# du-ino.net
KiCad netlist of a schematic drawn in EAGLE
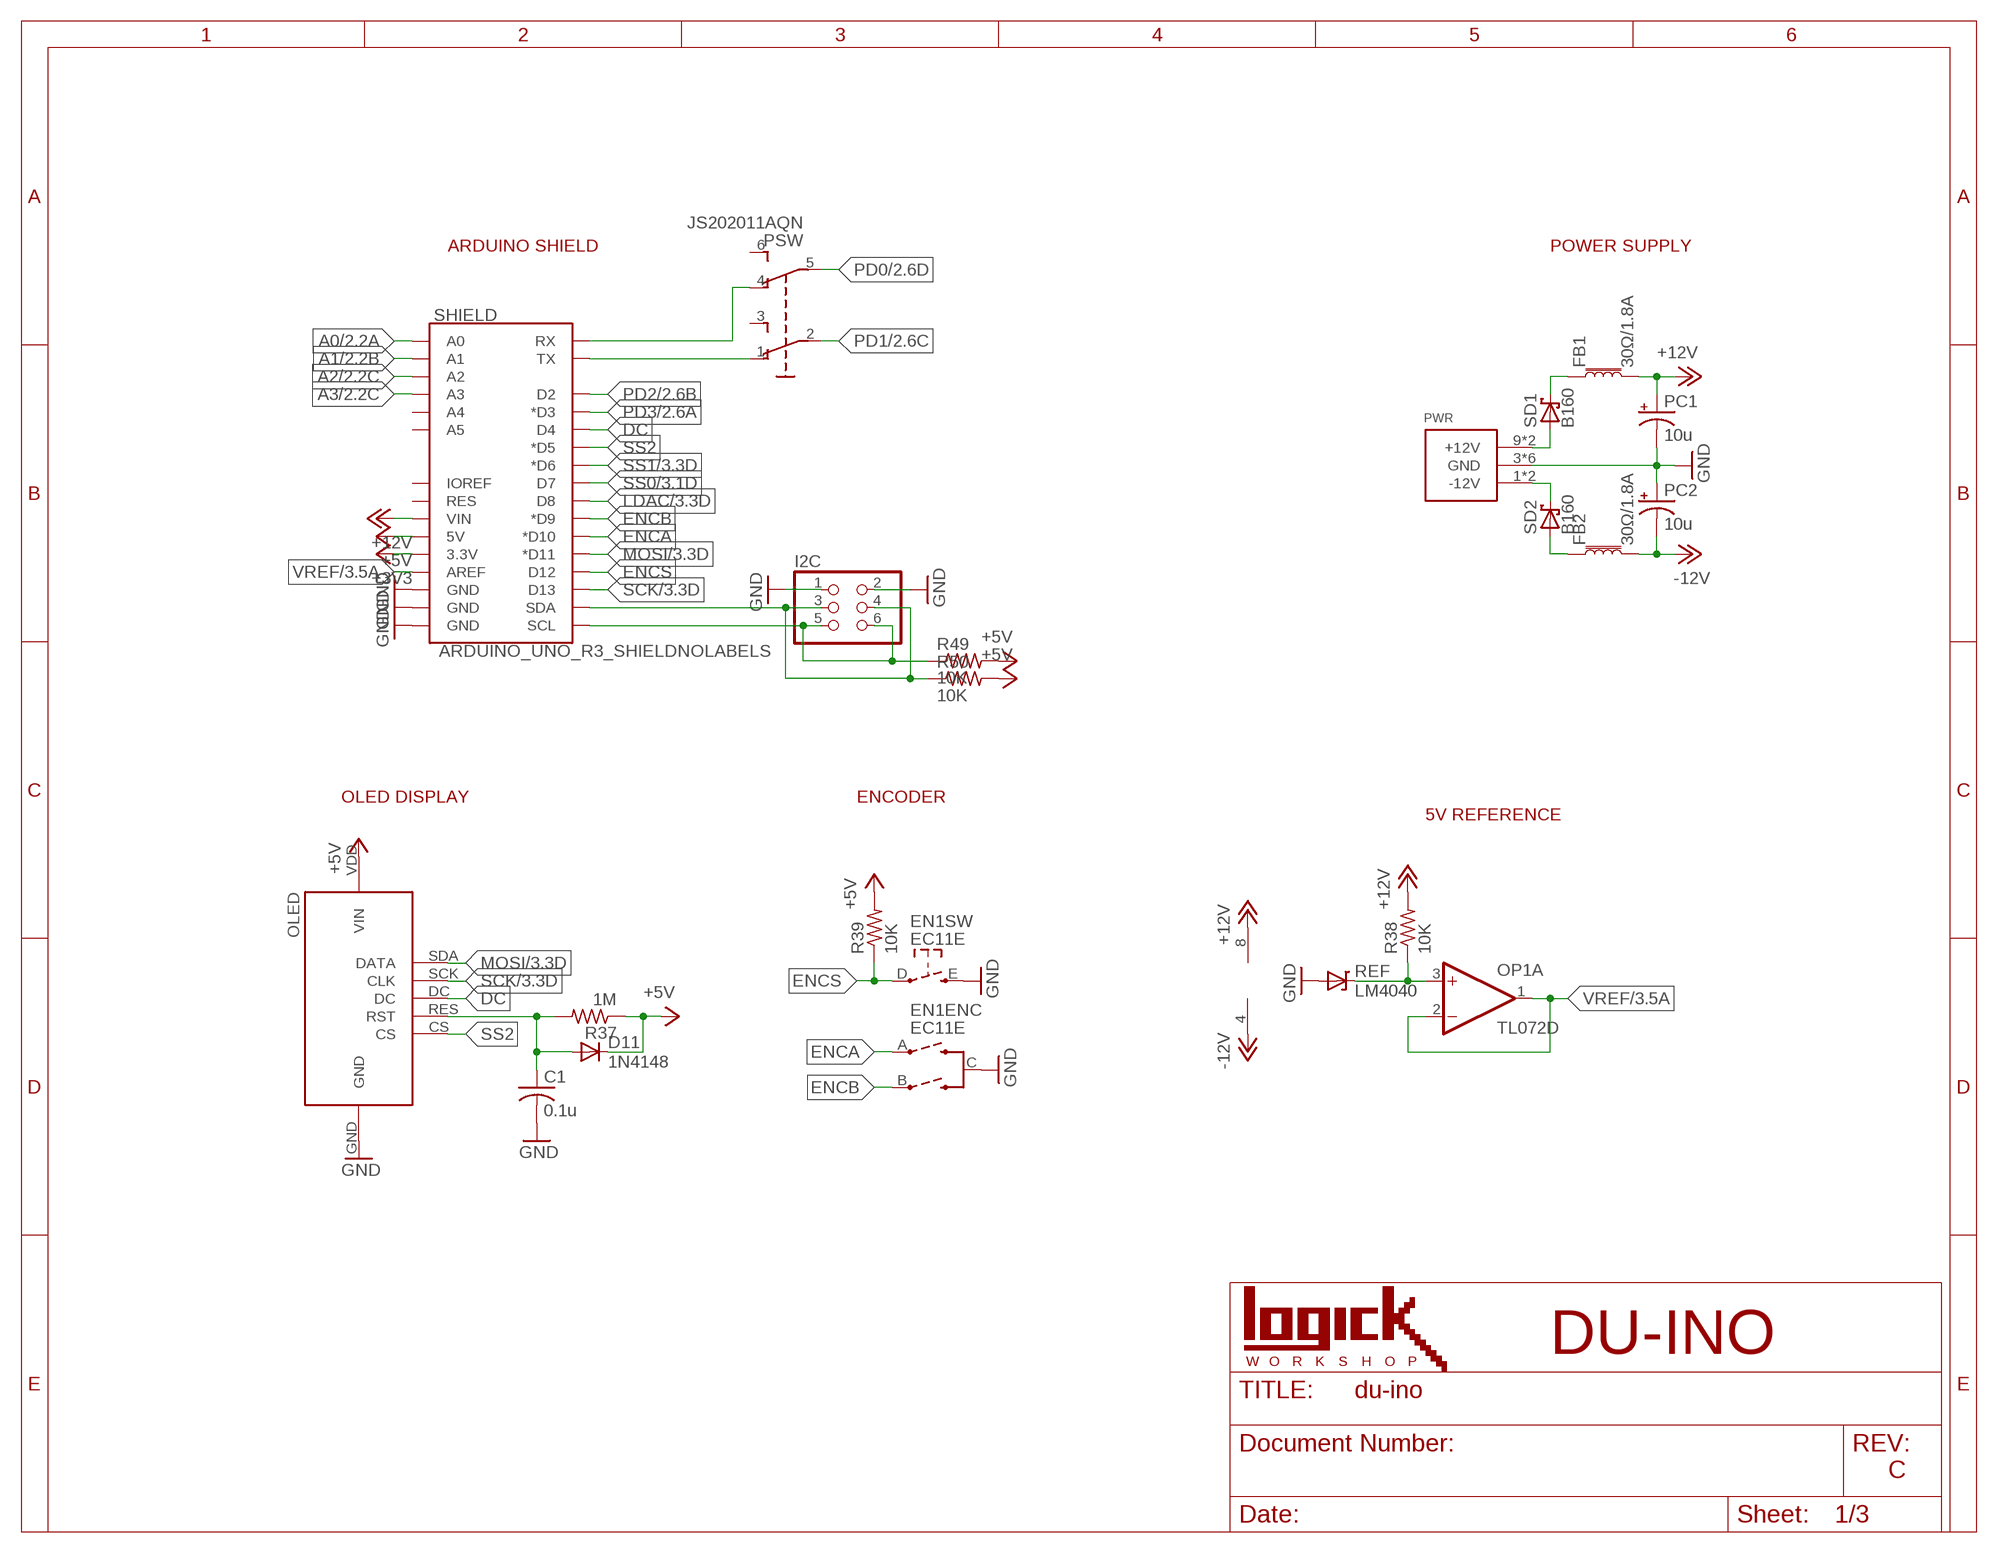
[diagram p0: schematic, sheet 1]
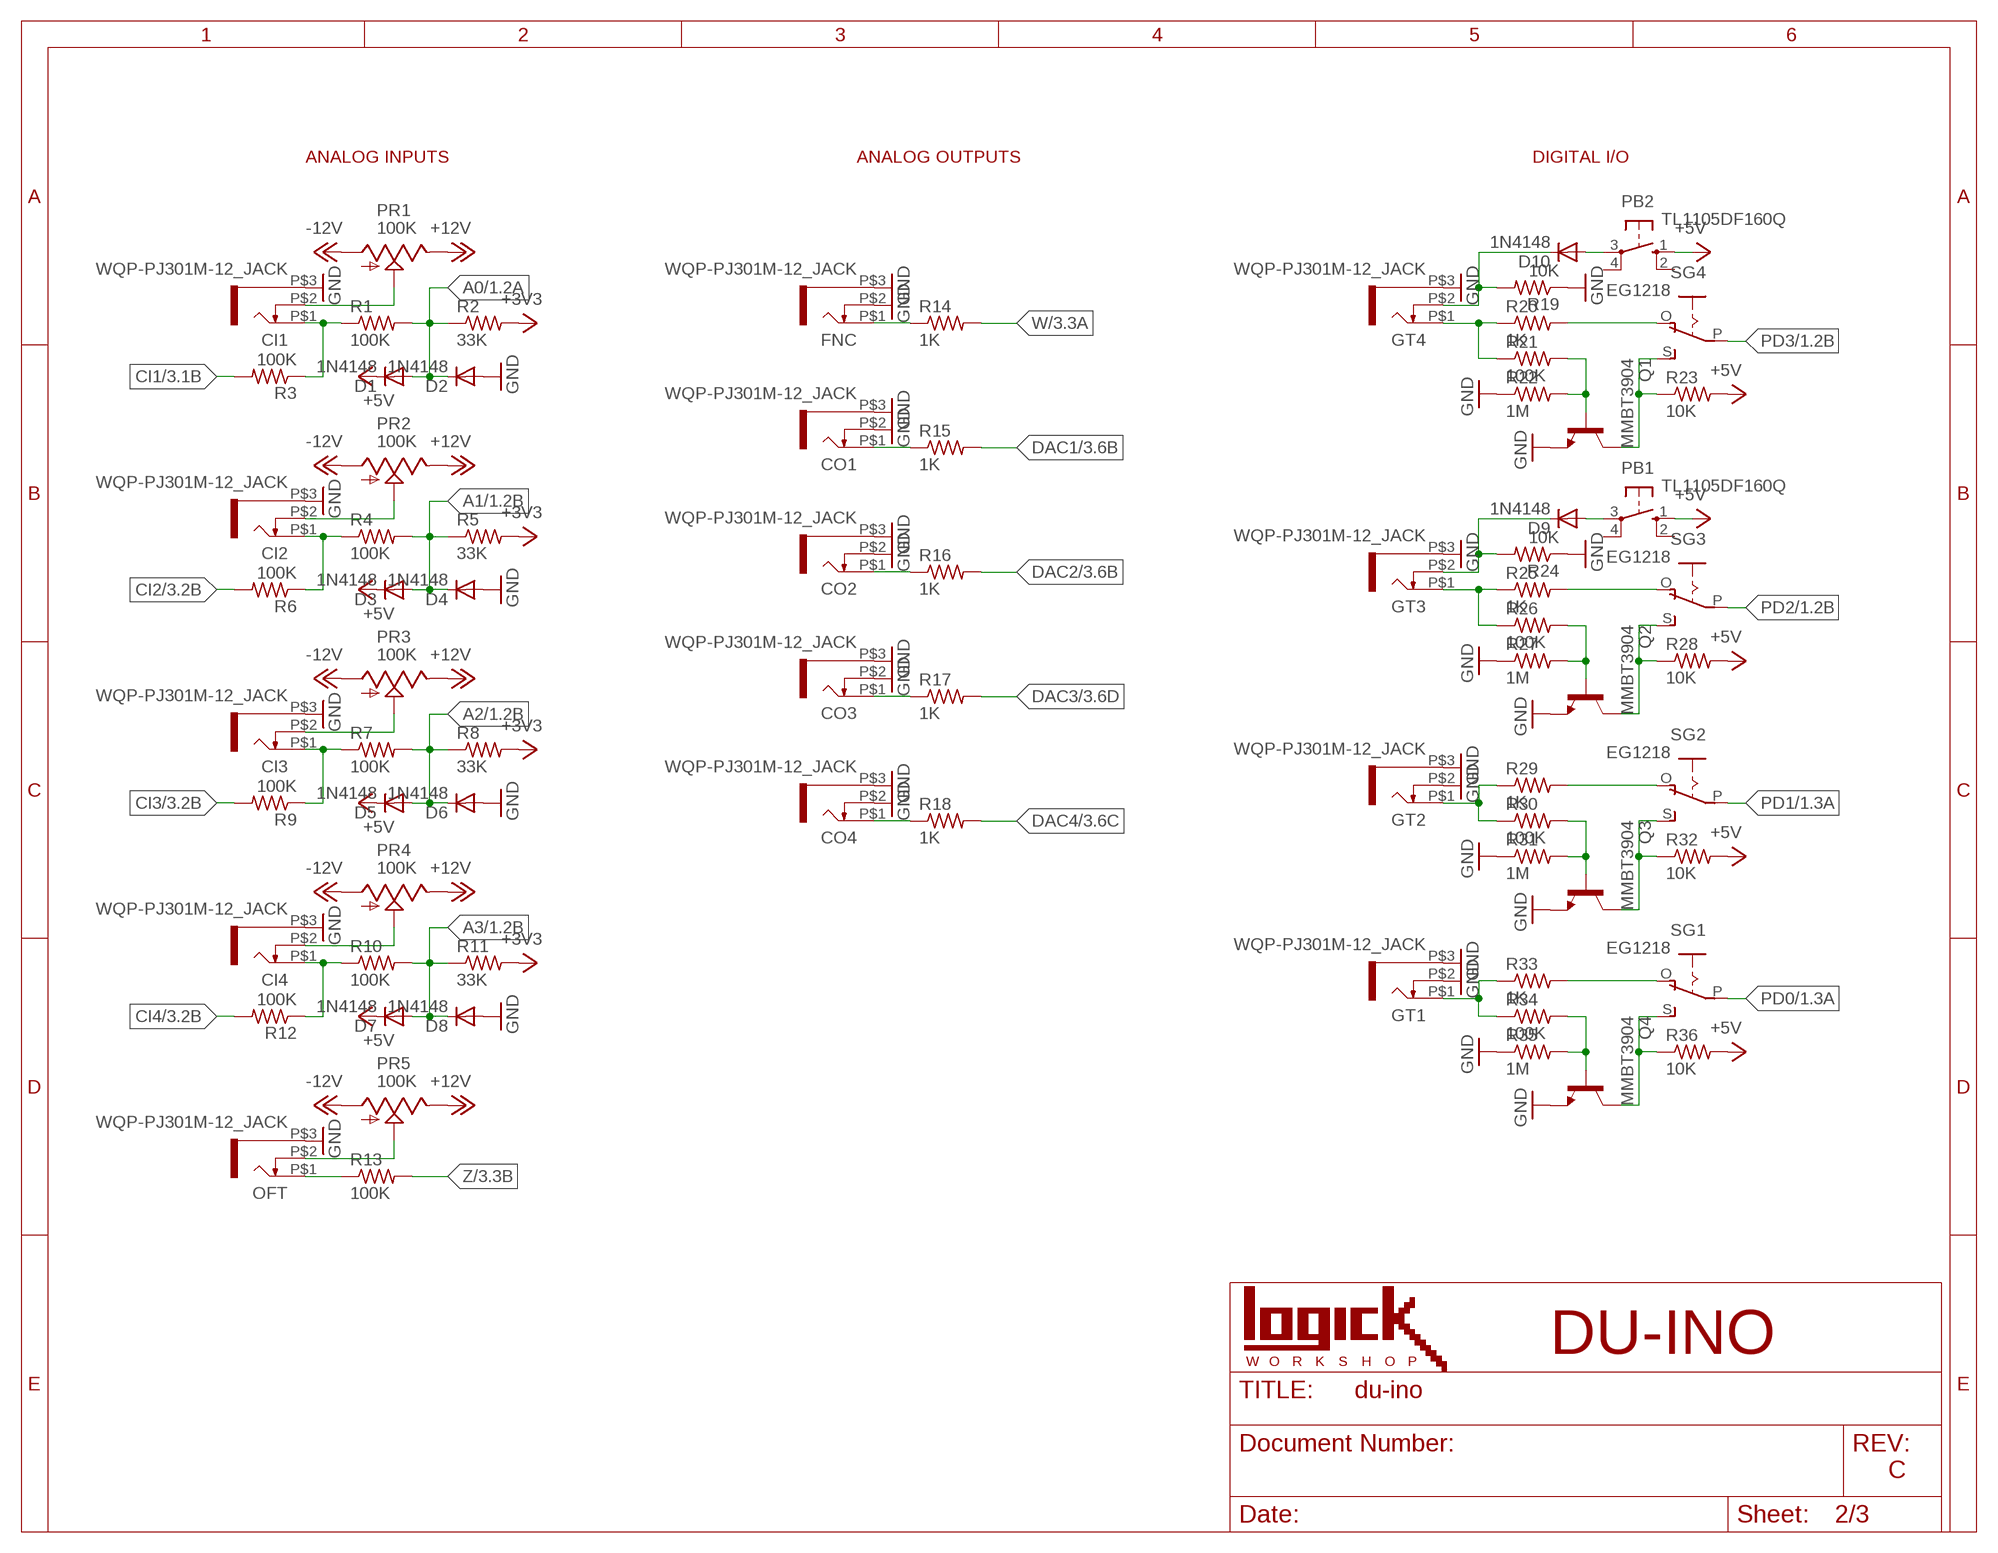
[diagram p1: schematic, sheet 2]
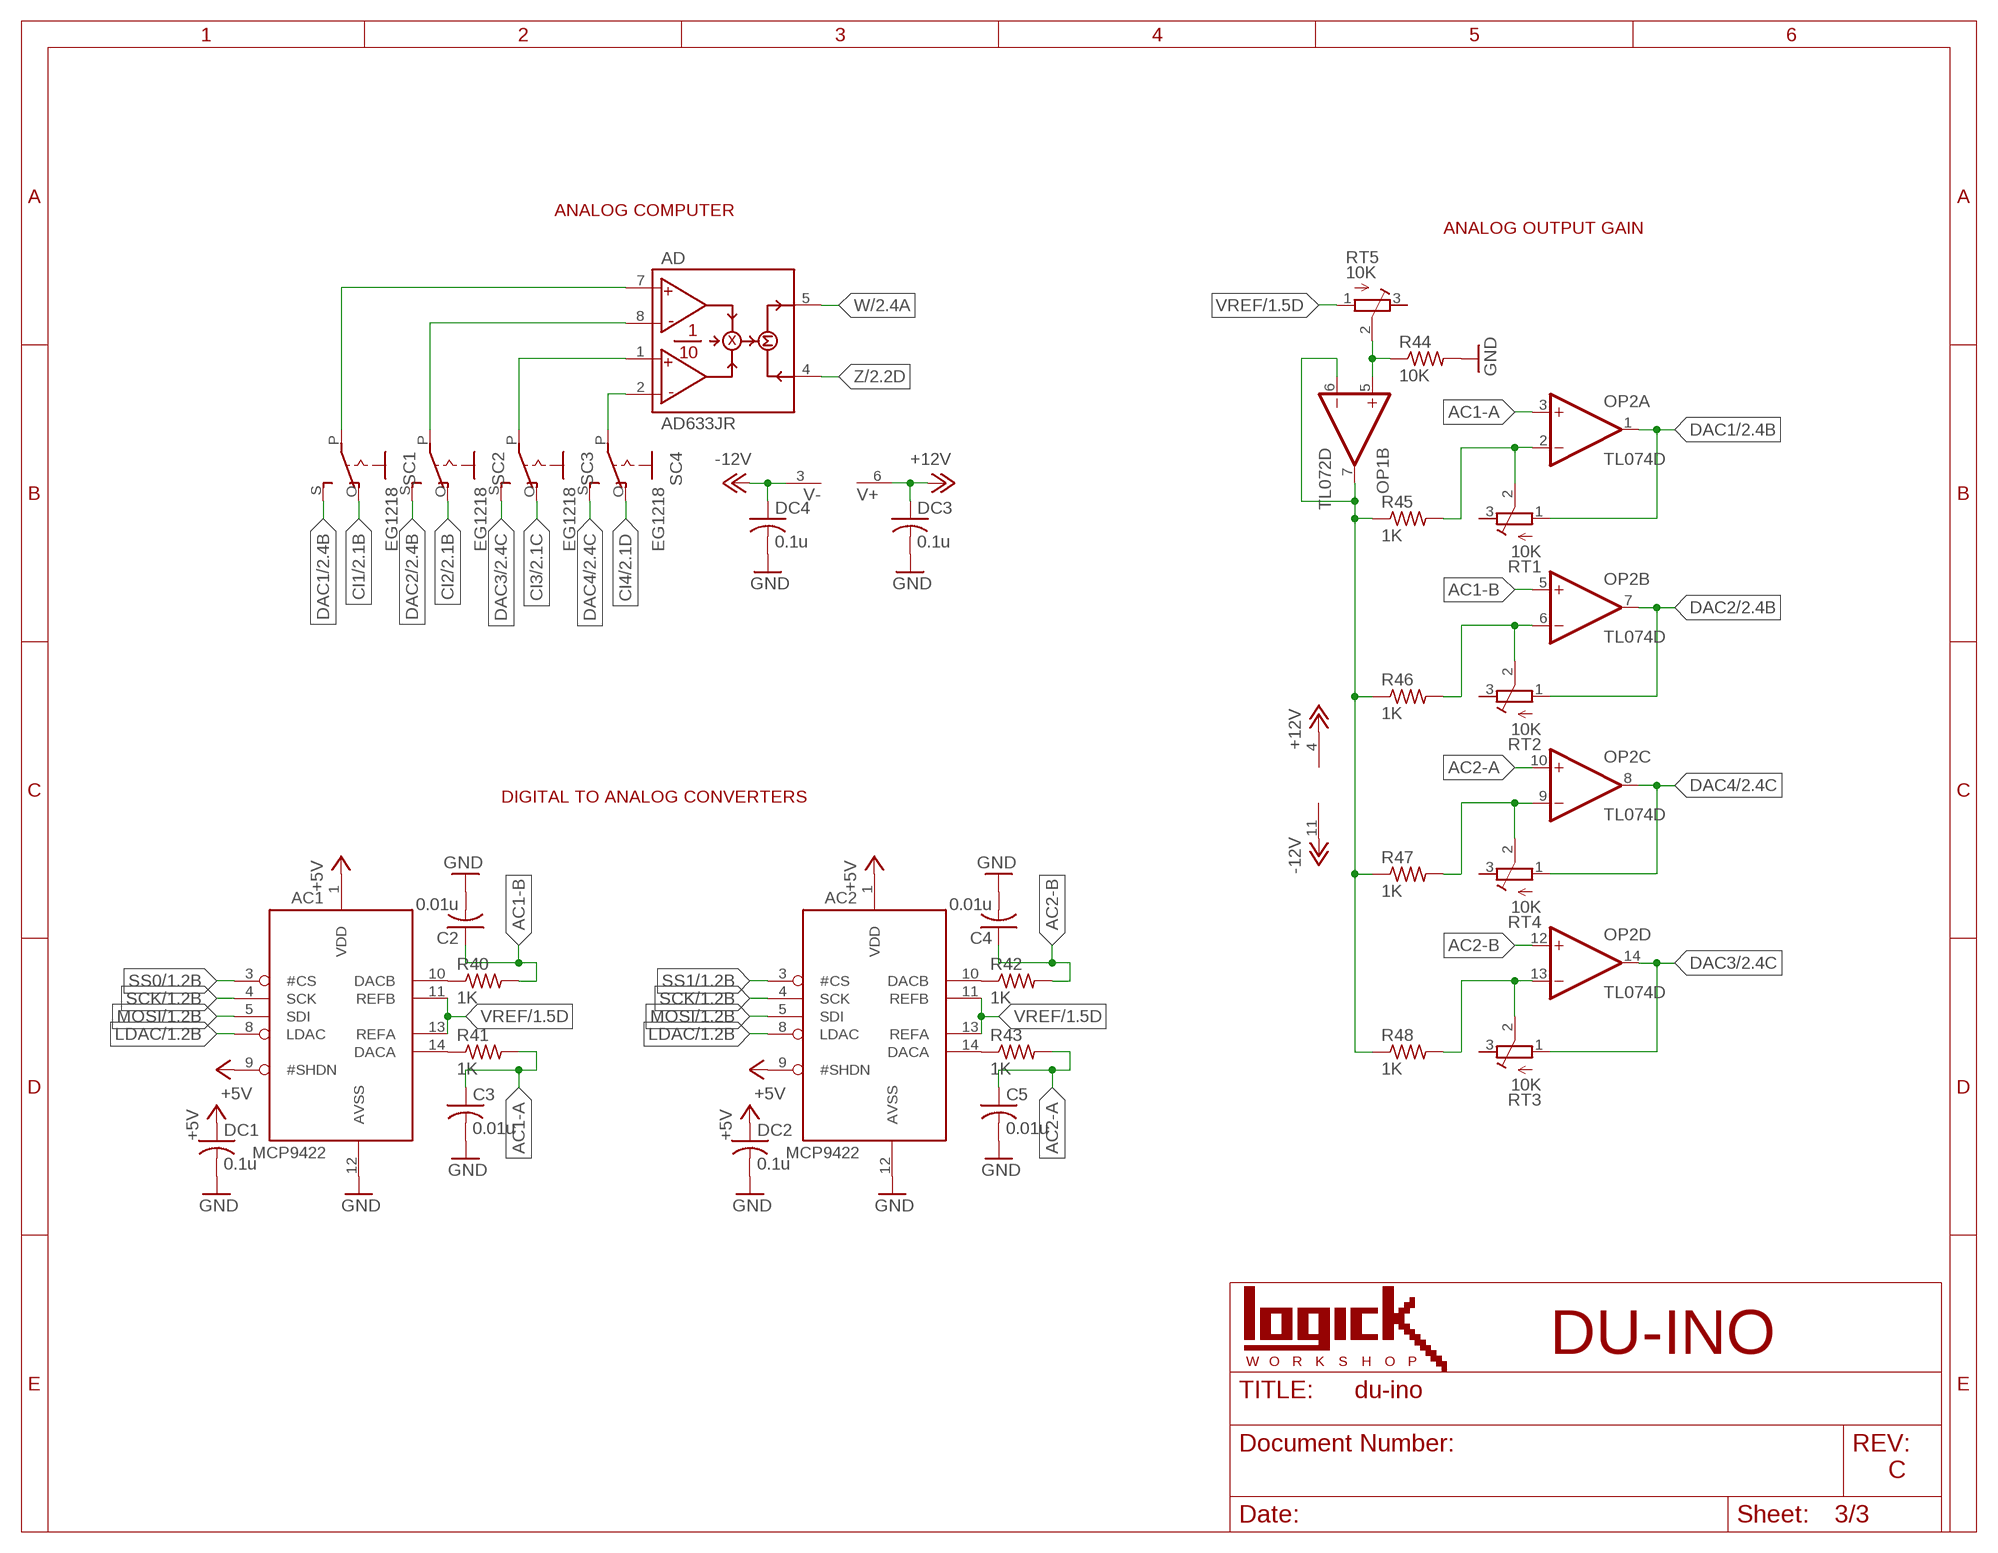
[diagram p2: schematic, sheet 3]

(export (version "E")
  (design (tool "Eeschema 10.0.6"))
  (components
    (comp (ref "CI1")
      (value "WQP-PJ301M-12_JACK")
      (footprint "eagle-import:WQP-PJ301M-12_JACK")
      (libsource (lib "eagle-import") (part "WQP-PJ301M-12_JACK"))
    )
    (comp (ref "CI2")
      (value "WQP-PJ301M-12_JACK")
      (footprint "eagle-import:WQP-PJ301M-12_JACK")
      (libsource (lib "eagle-import") (part "WQP-PJ301M-12_JACK"))
    )
    (comp (ref "CI3")
      (value "WQP-PJ301M-12_JACK")
      (footprint "eagle-import:WQP-PJ301M-12_JACK")
      (libsource (lib "eagle-import") (part "WQP-PJ301M-12_JACK"))
    )
    (comp (ref "CI4")
      (value "WQP-PJ301M-12_JACK")
      (footprint "eagle-import:WQP-PJ301M-12_JACK")
      (libsource (lib "eagle-import") (part "WQP-PJ301M-12_JACK"))
    )
    (comp (ref "CO1")
      (value "WQP-PJ301M-12_JACK")
      (footprint "eagle-import:WQP-PJ301M-12_JACK")
      (libsource (lib "eagle-import") (part "WQP-PJ301M-12_JACK"))
    )
    (comp (ref "CO2")
      (value "WQP-PJ301M-12_JACK")
      (footprint "eagle-import:WQP-PJ301M-12_JACK")
      (libsource (lib "eagle-import") (part "WQP-PJ301M-12_JACK"))
    )
    (comp (ref "CO3")
      (value "WQP-PJ301M-12_JACK")
      (footprint "eagle-import:WQP-PJ301M-12_JACK")
      (libsource (lib "eagle-import") (part "WQP-PJ301M-12_JACK"))
    )
    (comp (ref "CO4")
      (value "WQP-PJ301M-12_JACK")
      (footprint "eagle-import:WQP-PJ301M-12_JACK")
      (libsource (lib "eagle-import") (part "WQP-PJ301M-12_JACK"))
    )
    (comp (ref "D1")
      (value "1N4148")
      (footprint "eagle-import:SOD123")
      (libsource (lib "eagle-import") (part "DIODE-SOD123"))
    )
    (comp (ref "D2")
      (value "1N4148")
      (footprint "eagle-import:SOD123")
      (libsource (lib "eagle-import") (part "DIODE-SOD123"))
    )
    (comp (ref "D3")
      (value "1N4148")
      (footprint "eagle-import:SOD123")
      (libsource (lib "eagle-import") (part "DIODE-SOD123"))
    )
    (comp (ref "D4")
      (value "1N4148")
      (footprint "eagle-import:SOD123")
      (libsource (lib "eagle-import") (part "DIODE-SOD123"))
    )
    (comp (ref "D5")
      (value "1N4148")
      (footprint "eagle-import:SOD123")
      (libsource (lib "eagle-import") (part "DIODE-SOD123"))
    )
    (comp (ref "D6")
      (value "1N4148")
      (footprint "eagle-import:SOD123")
      (libsource (lib "eagle-import") (part "DIODE-SOD123"))
    )
    (comp (ref "D7")
      (value "1N4148")
      (footprint "eagle-import:SOD123")
      (libsource (lib "eagle-import") (part "DIODE-SOD123"))
    )
    (comp (ref "D8")
      (value "1N4148")
      (footprint "eagle-import:SOD123")
      (libsource (lib "eagle-import") (part "DIODE-SOD123"))
    )
    (comp (ref "D9")
      (value "1N4148")
      (footprint "eagle-import:SOD123")
      (libsource (lib "eagle-import") (part "DIODE-SOD123"))
    )
    (comp (ref "D10")
      (value "1N4148")
      (footprint "eagle-import:SOD123")
      (libsource (lib "eagle-import") (part "DIODE-SOD123"))
    )
    (comp (ref "FNC")
      (value "WQP-PJ301M-12_JACK")
      (footprint "eagle-import:WQP-PJ301M-12_JACK")
      (libsource (lib "eagle-import") (part "WQP-PJ301M-12_JACK"))
    )
    (comp (ref "GT1")
      (value "WQP-PJ301M-12_JACK")
      (footprint "eagle-import:WQP-PJ301M-12_JACK")
      (libsource (lib "eagle-import") (part "WQP-PJ301M-12_JACK"))
    )
    (comp (ref "GT2")
      (value "WQP-PJ301M-12_JACK")
      (footprint "eagle-import:WQP-PJ301M-12_JACK")
      (libsource (lib "eagle-import") (part "WQP-PJ301M-12_JACK"))
    )
    (comp (ref "GT3")
      (value "WQP-PJ301M-12_JACK")
      (footprint "eagle-import:WQP-PJ301M-12_JACK")
      (libsource (lib "eagle-import") (part "WQP-PJ301M-12_JACK"))
    )
    (comp (ref "GT4")
      (value "WQP-PJ301M-12_JACK")
      (footprint "eagle-import:WQP-PJ301M-12_JACK")
      (libsource (lib "eagle-import") (part "WQP-PJ301M-12_JACK"))
    )
    (comp (ref "OFT")
      (value "WQP-PJ301M-12_JACK")
      (footprint "eagle-import:WQP-PJ301M-12_JACK")
      (libsource (lib "eagle-import") (part "WQP-PJ301M-12_JACK"))
    )
    (comp (ref "PB1")
      (value "TL1105DF160Q")
      (footprint "eagle-import:B3F-10XX")
      (fields (field (name "MPN") "B3F-1000"))
      (libsource (lib "eagle-import") (part "10-XX"))
    )
    (comp (ref "PB2")
      (value "TL1105DF160Q")
      (footprint "eagle-import:B3F-10XX")
      (fields (field (name "MPN") "B3F-1000"))
      (libsource (lib "eagle-import") (part "10-XX"))
    )
    (comp (ref "PR1")
      (value "100K")
      (footprint "eagle-import:R0904N")
      (libsource (lib "eagle-import") (part "R0904N"))
    )
    (comp (ref "PR2")
      (value "100K")
      (footprint "eagle-import:R0904N")
      (libsource (lib "eagle-import") (part "R0904N"))
    )
    (comp (ref "PR3")
      (value "100K")
      (footprint "eagle-import:R0904N")
      (libsource (lib "eagle-import") (part "R0904N"))
    )
    (comp (ref "PR4")
      (value "100K")
      (footprint "eagle-import:R0904N")
      (libsource (lib "eagle-import") (part "R0904N"))
    )
    (comp (ref "PR5")
      (value "100K")
      (footprint "eagle-import:R0904N")
      (libsource (lib "eagle-import") (part "R0904N"))
    )
    (comp (ref "Q1")
      (value "MMBT3904")
      (footprint "eagle-import:SOT23-BEC")
      (libsource (lib "eagle-import") (part "-NPN-SOT23-BECMMBT3904LT1"))
    )
    (comp (ref "Q2")
      (value "MMBT3904")
      (footprint "eagle-import:SOT23-BEC")
      (libsource (lib "eagle-import") (part "-NPN-SOT23-BECMMBT3904LT1"))
    )
    (comp (ref "Q3")
      (value "MMBT3904")
      (footprint "eagle-import:SOT23-BEC")
      (libsource (lib "eagle-import") (part "-NPN-SOT23-BECMMBT3904LT1"))
    )
    (comp (ref "Q4")
      (value "MMBT3904")
      (footprint "eagle-import:SOT23-BEC")
      (libsource (lib "eagle-import") (part "-NPN-SOT23-BECMMBT3904LT1"))
    )
    (comp (ref "R1")
      (value "100K")
      (footprint "eagle-import:R0603")
      (libsource (lib "eagle-import") (part "R-US_R0603"))
    )
    (comp (ref "R2")
      (value "33K")
      (footprint "eagle-import:R0603")
      (libsource (lib "eagle-import") (part "R-US_R0603"))
    )
    (comp (ref "R3")
      (value "100K")
      (footprint "eagle-import:R0603")
      (libsource (lib "eagle-import") (part "R-US_R0603"))
    )
    (comp (ref "R4")
      (value "100K")
      (footprint "eagle-import:R0603")
      (libsource (lib "eagle-import") (part "R-US_R0603"))
    )
    (comp (ref "R5")
      (value "33K")
      (footprint "eagle-import:R0603")
      (libsource (lib "eagle-import") (part "R-US_R0603"))
    )
    (comp (ref "R6")
      (value "100K")
      (footprint "eagle-import:R0603")
      (libsource (lib "eagle-import") (part "R-US_R0603"))
    )
    (comp (ref "R7")
      (value "100K")
      (footprint "eagle-import:R0603")
      (libsource (lib "eagle-import") (part "R-US_R0603"))
    )
    (comp (ref "R8")
      (value "33K")
      (footprint "eagle-import:R0603")
      (libsource (lib "eagle-import") (part "R-US_R0603"))
    )
    (comp (ref "R9")
      (value "100K")
      (footprint "eagle-import:R0603")
      (libsource (lib "eagle-import") (part "R-US_R0603"))
    )
    (comp (ref "R10")
      (value "100K")
      (footprint "eagle-import:R0603")
      (libsource (lib "eagle-import") (part "R-US_R0603"))
    )
    (comp (ref "R11")
      (value "33K")
      (footprint "eagle-import:R0603")
      (libsource (lib "eagle-import") (part "R-US_R0603"))
    )
    (comp (ref "R12")
      (value "100K")
      (footprint "eagle-import:R0603")
      (libsource (lib "eagle-import") (part "R-US_R0603"))
    )
    (comp (ref "R13")
      (value "100K")
      (footprint "eagle-import:R0603")
      (libsource (lib "eagle-import") (part "R-US_R0603"))
    )
    (comp (ref "R14")
      (value "1K")
      (footprint "eagle-import:R0603")
      (libsource (lib "eagle-import") (part "R-US_R0603"))
    )
    (comp (ref "R15")
      (value "1K")
      (footprint "eagle-import:R0603")
      (libsource (lib "eagle-import") (part "R-US_R0603"))
    )
    (comp (ref "R16")
      (value "1K")
      (footprint "eagle-import:R0603")
      (libsource (lib "eagle-import") (part "R-US_R0603"))
    )
    (comp (ref "R17")
      (value "1K")
      (footprint "eagle-import:R0603")
      (libsource (lib "eagle-import") (part "R-US_R0603"))
    )
    (comp (ref "R18")
      (value "1K")
      (footprint "eagle-import:R0603")
      (libsource (lib "eagle-import") (part "R-US_R0603"))
    )
    (comp (ref "R19")
      (value "10K")
      (footprint "eagle-import:R0603")
      (libsource (lib "eagle-import") (part "resistor_R-US_R0603"))
    )
    (comp (ref "R20")
      (value "1K")
      (footprint "eagle-import:R0603")
      (libsource (lib "eagle-import") (part "R-US_R0603"))
    )
    (comp (ref "R21")
      (value "100K")
      (footprint "eagle-import:R0603")
      (libsource (lib "eagle-import") (part "R-US_R0603"))
    )
    (comp (ref "R22")
      (value "1M")
      (footprint "eagle-import:R0603")
      (libsource (lib "eagle-import") (part "R-US_R0603"))
    )
    (comp (ref "R23")
      (value "10K")
      (footprint "eagle-import:R0603")
      (libsource (lib "eagle-import") (part "R-US_R0603"))
    )
    (comp (ref "R24")
      (value "10K")
      (footprint "eagle-import:R0603")
      (libsource (lib "eagle-import") (part "resistor_R-US_R0603"))
    )
    (comp (ref "R25")
      (value "1K")
      (footprint "eagle-import:R0603")
      (libsource (lib "eagle-import") (part "R-US_R0603"))
    )
    (comp (ref "R26")
      (value "100K")
      (footprint "eagle-import:R0603")
      (libsource (lib "eagle-import") (part "R-US_R0603"))
    )
    (comp (ref "R27")
      (value "1M")
      (footprint "eagle-import:R0603")
      (libsource (lib "eagle-import") (part "R-US_R0603"))
    )
    (comp (ref "R28")
      (value "10K")
      (footprint "eagle-import:R0603")
      (libsource (lib "eagle-import") (part "R-US_R0603"))
    )
    (comp (ref "R29")
      (value "1K")
      (footprint "eagle-import:R0603")
      (libsource (lib "eagle-import") (part "R-US_R0603"))
    )
    (comp (ref "R30")
      (value "100K")
      (footprint "eagle-import:R0603")
      (libsource (lib "eagle-import") (part "R-US_R0603"))
    )
    (comp (ref "R31")
      (value "1M")
      (footprint "eagle-import:R0603")
      (libsource (lib "eagle-import") (part "R-US_R0603"))
    )
    (comp (ref "R32")
      (value "10K")
      (footprint "eagle-import:R0603")
      (libsource (lib "eagle-import") (part "R-US_R0603"))
    )
    (comp (ref "R33")
      (value "1K")
      (footprint "eagle-import:R0603")
      (libsource (lib "eagle-import") (part "R-US_R0603"))
    )
    (comp (ref "R34")
      (value "100K")
      (footprint "eagle-import:R0603")
      (libsource (lib "eagle-import") (part "R-US_R0603"))
    )
    (comp (ref "R35")
      (value "1M")
      (footprint "eagle-import:R0603")
      (libsource (lib "eagle-import") (part "R-US_R0603"))
    )
    (comp (ref "R36")
      (value "10K")
      (footprint "eagle-import:R0603")
      (libsource (lib "eagle-import") (part "R-US_R0603"))
    )
    (comp (ref "SG1")
      (value "EG1218")
      (footprint "eagle-import:EG1218")
      (libsource (lib "eagle-import") (part "EG1218S"))
    )
    (comp (ref "SG2")
      (value "EG1218")
      (footprint "eagle-import:EG1218")
      (libsource (lib "eagle-import") (part "EG1218S"))
    )
    (comp (ref "SG3")
      (value "EG1218")
      (footprint "eagle-import:EG1218")
      (libsource (lib "eagle-import") (part "EG1218S"))
    )
    (comp (ref "SG4")
      (value "EG1218")
      (footprint "eagle-import:EG1218")
      (libsource (lib "eagle-import") (part "EG1218S"))
    )
    (comp (ref "AC1")
      (value "MCP4922E/SL")
      (footprint "eagle-import:SO14")
      (libsource (lib "eagle-import") (part "MCP4922E/SL"))
    )
    (comp (ref "AC2")
      (value "MCP4922E/SL")
      (footprint "eagle-import:SO14")
      (libsource (lib "eagle-import") (part "MCP4922E/SL"))
    )
    (comp (ref "AD")
      (value "AD633JR")
      (footprint "eagle-import:SO8")
      (libsource (lib "eagle-import") (part "AD633RJ"))
    )
    (comp (ref "C2")
      (value "0.01u")
      (footprint "eagle-import:C0603")
      (libsource (lib "eagle-import") (part "C-USC0603"))
    )
    (comp (ref "C3")
      (value "0.01u")
      (footprint "eagle-import:C0603")
      (libsource (lib "eagle-import") (part "C-USC0603"))
    )
    (comp (ref "C4")
      (value "0.01u")
      (footprint "eagle-import:C0603")
      (libsource (lib "eagle-import") (part "C-USC0603"))
    )
    (comp (ref "C5")
      (value "0.01u")
      (footprint "eagle-import:C0603")
      (libsource (lib "eagle-import") (part "C-USC0603"))
    )
    (comp (ref "DC1")
      (value "0.1u")
      (footprint "eagle-import:C0603")
      (libsource (lib "eagle-import") (part "C-USC0603"))
    )
    (comp (ref "DC2")
      (value "0.1u")
      (footprint "eagle-import:C0603")
      (libsource (lib "eagle-import") (part "C-USC0603"))
    )
    (comp (ref "DC3")
      (value "0.1u")
      (footprint "eagle-import:C0603")
      (libsource (lib "eagle-import") (part "C-USC0603"))
    )
    (comp (ref "DC4")
      (value "0.1u")
      (footprint "eagle-import:C0603")
      (libsource (lib "eagle-import") (part "C-USC0603"))
    )
    (comp (ref "OP1")
      (value "TL072D")
      (footprint "eagle-import:SO08")
      (libsource (lib "eagle-import") (part "TL072D"))
    )
    (comp (ref "OP2")
      (value "TL074D")
      (footprint "eagle-import:SO14")
      (libsource (lib "eagle-import") (part "TL074D"))
    )
    (comp (ref "R40")
      (value "1K")
      (footprint "eagle-import:R0603")
      (libsource (lib "eagle-import") (part "R-US_R0603"))
    )
    (comp (ref "R41")
      (value "1K")
      (footprint "eagle-import:R0603")
      (libsource (lib "eagle-import") (part "R-US_R0603"))
    )
    (comp (ref "R42")
      (value "1K")
      (footprint "eagle-import:R0603")
      (libsource (lib "eagle-import") (part "R-US_R0603"))
    )
    (comp (ref "R43")
      (value "1K")
      (footprint "eagle-import:R0603")
      (libsource (lib "eagle-import") (part "R-US_R0603"))
    )
    (comp (ref "R44")
      (value "10K")
      (footprint "eagle-import:R0603")
      (libsource (lib "eagle-import") (part "R-US_R0603"))
    )
    (comp (ref "R45")
      (value "1K")
      (footprint "eagle-import:R0603")
      (libsource (lib "eagle-import") (part "R-US_R0603"))
    )
    (comp (ref "R46")
      (value "1K")
      (footprint "eagle-import:R0603")
      (libsource (lib "eagle-import") (part "R-US_R0603"))
    )
    (comp (ref "R47")
      (value "1K")
      (footprint "eagle-import:R0603")
      (libsource (lib "eagle-import") (part "R-US_R0603"))
    )
    (comp (ref "R48")
      (value "1K")
      (footprint "eagle-import:R0603")
      (libsource (lib "eagle-import") (part "R-US_R0603"))
    )
    (comp (ref "RT1")
      (value "10K")
      (footprint "eagle-import:RTRIM3296W")
      (libsource (lib "eagle-import") (part "R-TRIMM3296W"))
    )
    (comp (ref "RT2")
      (value "10K")
      (footprint "eagle-import:RTRIM3296W")
      (libsource (lib "eagle-import") (part "R-TRIMM3296W"))
    )
    (comp (ref "RT3")
      (value "10K")
      (footprint "eagle-import:RTRIM3296W")
      (libsource (lib "eagle-import") (part "R-TRIMM3296W"))
    )
    (comp (ref "RT4")
      (value "10K")
      (footprint "eagle-import:RTRIM3296W")
      (libsource (lib "eagle-import") (part "R-TRIMM3296W"))
    )
    (comp (ref "RT5")
      (value "10K")
      (footprint "eagle-import:RTRIM3296W")
      (libsource (lib "eagle-import") (part "R-TRIMM3296W"))
    )
    (comp (ref "SC1")
      (value "EG1218")
      (footprint "eagle-import:EG1218")
      (libsource (lib "eagle-import") (part "EG1218S"))
    )
    (comp (ref "SC2")
      (value "EG1218")
      (footprint "eagle-import:EG1218")
      (libsource (lib "eagle-import") (part "EG1218S"))
    )
    (comp (ref "SC3")
      (value "EG1218")
      (footprint "eagle-import:EG1218")
      (libsource (lib "eagle-import") (part "EG1218S"))
    )
    (comp (ref "SC4")
      (value "EG1218")
      (footprint "eagle-import:EG1218")
      (libsource (lib "eagle-import") (part "EG1218S"))
    )
    (comp (ref "C1")
      (value "0.1u")
      (footprint "eagle-import:C0603")
      (libsource (lib "eagle-import") (part "C-USC0603"))
    )
    (comp (ref "D11")
      (value "1N4148")
      (footprint "eagle-import:SOD123")
      (libsource (lib "eagle-import") (part "DIODE-SOD123"))
    )
    (comp (ref "EN1")
      (value "EC11E")
      (footprint "eagle-import:EC11E")
      (libsource (lib "eagle-import") (part "EC11E"))
    )
    (comp (ref "FB1")
      (value "30Ω/1.8A")
      (footprint "eagle-import:0603")
      (libsource (lib "eagle-import") (part "FERRITE_BEAD-0603"))
    )
    (comp (ref "FB2")
      (value "30Ω/1.8A")
      (footprint "eagle-import:0603")
      (libsource (lib "eagle-import") (part "FERRITE_BEAD-0603"))
    )
    (comp (ref "I2C")
      (value "PINHD-2X3")
      (footprint "eagle-import:2X03")
      (libsource (lib "eagle-import") (part "PINHD-2X3"))
    )
    (comp (ref "OLED")
      (value "OLED-SAMIORE")
      (footprint "eagle-import:OLED-SAMIORE")
      (libsource (lib "eagle-import") (part "OLED-SAMIORE"))
    )
    (comp (ref "PC1")
      (value "10u")
      (footprint "eagle-import:PANASONIC_B")
      (libsource (lib "eagle-import") (part "CPOL-USB"))
    )
    (comp (ref "PC2")
      (value "10u")
      (footprint "eagle-import:PANASONIC_B")
      (libsource (lib "eagle-import") (part "CPOL-USB"))
    )
    (comp (ref "PSW")
      (value "JS202011AQN")
      (footprint "eagle-import:JS202011AQN")
      (libsource (lib "eagle-import") (part "JS202011AQN"))
    )
    (comp (ref "PWR")
      (value "POWER_SIMPLE10")
      (footprint "eagle-import:POWER_10")
      (libsource (lib "eagle-import") (part "POWER_SIMPLE10"))
    )
    (comp (ref "R37")
      (value "1M")
      (footprint "eagle-import:R0603")
      (libsource (lib "eagle-import") (part "R-US_R0603"))
    )
    (comp (ref "R38")
      (value "10K")
      (footprint "eagle-import:R0603")
      (libsource (lib "eagle-import") (part "R-US_R0603"))
    )
    (comp (ref "R39")
      (value "10K")
      (footprint "eagle-import:R0603")
      (libsource (lib "eagle-import") (part "R-US_R0603"))
    )
    (comp (ref "R49")
      (value "10K")
      (footprint "eagle-import:R0603")
      (libsource (lib "eagle-import") (part "R-US_R0603"))
    )
    (comp (ref "R50")
      (value "10K")
      (footprint "eagle-import:R0603")
      (libsource (lib "eagle-import") (part "R-US_R0603"))
    )
    (comp (ref "REF")
      (value "LM4040")
      (footprint "eagle-import:SOT23")
      (libsource (lib "eagle-import") (part "LM4040"))
    )
    (comp (ref "SD1")
      (value "B160")
      (footprint "eagle-import:SMB")
      (libsource (lib "eagle-import") (part "SCHOTTKY-DIODESMD"))
    )
    (comp (ref "SD2")
      (value "B160")
      (footprint "eagle-import:SMB")
      (libsource (lib "eagle-import") (part "SCHOTTKY-DIODESMD"))
    )
    (comp (ref "SHIELD")
      (value "ARDUINO_UNO_R3_SHIELDNOLABELS")
      (footprint "eagle-import:UNO_R3_SHIELD_NOLABELS")
      (libsource (lib "eagle-import") (part "ARDUINO_UNO_R3_SHIELDNOLABELS"))
    )
  )
  (nets
    (net (code "1") (name "+3V3") (class "Default")
      (node (ref "R11") (pin "2") (pinfunction "2_2") (pintype "passive"))
      (node (ref "R2") (pin "2") (pinfunction "2_2") (pintype "passive"))
      (node (ref "R5") (pin "2") (pinfunction "2_2") (pintype "passive"))
      (node (ref "R8") (pin "2") (pinfunction "2_2") (pintype "passive"))
      (node (ref "SHIELD") (pin "3.3V") (pinfunction "3.3V_3.3V") (pintype "bidirectional"))
    )
    (net (code "2") (name "+5V") (class "Default")
      (node (ref "AC1") (pin "1") (pinfunction "VDD_1") (pintype "power_in"))
      (node (ref "AC1") (pin "9") (pinfunction "#SHDN_9") (pintype "input"))
      (node (ref "AC2") (pin "1") (pinfunction "VDD_1") (pintype "power_in"))
      (node (ref "AC2") (pin "9") (pinfunction "#SHDN_9") (pintype "input"))
      (node (ref "D1") (pin "C") (pinfunction "C_C") (pintype "passive"))
      (node (ref "D11") (pin "C") (pinfunction "C_C") (pintype "passive"))
      (node (ref "D3") (pin "C") (pinfunction "C_C") (pintype "passive"))
      (node (ref "D5") (pin "C") (pinfunction "C_C") (pintype "passive"))
      (node (ref "D7") (pin "C") (pinfunction "C_C") (pintype "passive"))
      (node (ref "DC1") (pin "1") (pinfunction "1_1") (pintype "passive"))
      (node (ref "DC2") (pin "1") (pinfunction "1_1") (pintype "passive"))
      (node (ref "OLED") (pin "VDD") (pinfunction "VIN_VDD") (pintype "power_in"))
      (node (ref "PB1") (pin "1") (pinfunction "S_1") (pintype "passive"))
      (node (ref "PB2") (pin "1") (pinfunction "S_1") (pintype "passive"))
      (node (ref "R23") (pin "2") (pinfunction "2_2") (pintype "passive"))
      (node (ref "R28") (pin "2") (pinfunction "2_2") (pintype "passive"))
      (node (ref "R32") (pin "2") (pinfunction "2_2") (pintype "passive"))
      (node (ref "R36") (pin "2") (pinfunction "2_2") (pintype "passive"))
      (node (ref "R37") (pin "1") (pinfunction "1_1") (pintype "passive"))
      (node (ref "R39") (pin "2") (pinfunction "2_2") (pintype "passive"))
      (node (ref "R49") (pin "2") (pinfunction "2_2") (pintype "passive"))
      (node (ref "R50") (pin "2") (pinfunction "2_2") (pintype "passive"))
      (node (ref "SHIELD") (pin "5V") (pinfunction "5V_5V") (pintype "bidirectional"))
    )
    (net (code "3") (name "+12V") (class "Default")
      (node (ref "AD") (pin "6") (pinfunction "V+_6") (pintype "power_in"))
      (node (ref "DC3") (pin "1") (pinfunction "1_1") (pintype "passive"))
      (node (ref "FB1") (pin "2") (pinfunction "2_2") (pintype "passive"))
      (node (ref "OP1") (pin "8") (pinfunction "V+_8") (pintype "power_in"))
      (node (ref "OP2") (pin "4") (pinfunction "V+_4") (pintype "power_in"))
      (node (ref "PC1") (pin "+") (pinfunction "+_+") (pintype "passive"))
      (node (ref "PR1") (pin "3") (pinfunction "E_3") (pintype "passive"))
      (node (ref "PR2") (pin "3") (pinfunction "E_3") (pintype "passive"))
      (node (ref "PR3") (pin "3") (pinfunction "E_3") (pintype "passive"))
      (node (ref "PR4") (pin "3") (pinfunction "E_3") (pintype "passive"))
      (node (ref "PR5") (pin "3") (pinfunction "E_3") (pintype "passive"))
      (node (ref "R38") (pin "2") (pinfunction "2_2") (pintype "passive"))
      (node (ref "SHIELD") (pin "VIN") (pinfunction "VIN_VIN") (pintype "bidirectional"))
    )
    (net (code "4") (name "-12V") (class "Default")
      (node (ref "AD") (pin "3") (pinfunction "V-_3") (pintype "power_in"))
      (node (ref "DC4") (pin "1") (pinfunction "1_1") (pintype "passive"))
      (node (ref "FB2") (pin "2") (pinfunction "2_2") (pintype "passive"))
      (node (ref "OP1") (pin "4") (pinfunction "V-_4") (pintype "power_in"))
      (node (ref "OP2") (pin "11") (pinfunction "V-_11") (pintype "power_in"))
      (node (ref "PC2") (pin "-") (pinfunction "-_-") (pintype "passive"))
      (node (ref "PR1") (pin "1") (pinfunction "A_1") (pintype "passive"))
      (node (ref "PR2") (pin "1") (pinfunction "A_1") (pintype "passive"))
      (node (ref "PR3") (pin "1") (pinfunction "A_1") (pintype "passive"))
      (node (ref "PR4") (pin "1") (pinfunction "A_1") (pintype "passive"))
      (node (ref "PR5") (pin "1") (pinfunction "A_1") (pintype "passive"))
    )
    (net (code "5") (name "A0") (class "Default")
      (node (ref "D1") (pin "A") (pinfunction "A_A") (pintype "passive"))
      (node (ref "D2") (pin "C") (pinfunction "C_C") (pintype "passive"))
      (node (ref "R1") (pin "2") (pinfunction "2_2") (pintype "passive"))
      (node (ref "R2") (pin "1") (pinfunction "1_1") (pintype "passive"))
      (node (ref "SHIELD") (pin "A0") (pinfunction "A0_A0") (pintype "bidirectional"))
    )
    (net (code "6") (name "A1") (class "Default")
      (node (ref "D3") (pin "A") (pinfunction "A_A") (pintype "passive"))
      (node (ref "D4") (pin "C") (pinfunction "C_C") (pintype "passive"))
      (node (ref "R4") (pin "2") (pinfunction "2_2") (pintype "passive"))
      (node (ref "R5") (pin "1") (pinfunction "1_1") (pintype "passive"))
      (node (ref "SHIELD") (pin "A1") (pinfunction "A1_A1") (pintype "bidirectional"))
    )
    (net (code "7") (name "A2") (class "Default")
      (node (ref "D5") (pin "A") (pinfunction "A_A") (pintype "passive"))
      (node (ref "D6") (pin "C") (pinfunction "C_C") (pintype "passive"))
      (node (ref "R7") (pin "2") (pinfunction "2_2") (pintype "passive"))
      (node (ref "R8") (pin "1") (pinfunction "1_1") (pintype "passive"))
      (node (ref "SHIELD") (pin "A2") (pinfunction "A2_A2") (pintype "bidirectional"))
    )
    (net (code "8") (name "A3") (class "Default")
      (node (ref "D7") (pin "A") (pinfunction "A_A") (pintype "passive"))
      (node (ref "D8") (pin "C") (pinfunction "C_C") (pintype "passive"))
      (node (ref "R10") (pin "2") (pinfunction "2_2") (pintype "passive"))
      (node (ref "R11") (pin "1") (pinfunction "1_1") (pintype "passive"))
      (node (ref "SHIELD") (pin "A3") (pinfunction "A3_A3") (pintype "bidirectional"))
    )
    (net (code "9") (name "AC1-A") (class "Default")
      (node (ref "C3") (pin "1") (pinfunction "1_1") (pintype "passive"))
      (node (ref "OP2") (pin "3") (pinfunction "+IN_3") (pintype "input"))
      (node (ref "R41") (pin "2") (pinfunction "2_2") (pintype "passive"))
    )
    (net (code "10") (name "AC1-B") (class "Default")
      (node (ref "C2") (pin "1") (pinfunction "1_1") (pintype "passive"))
      (node (ref "OP2") (pin "5") (pinfunction "+IN_5") (pintype "input"))
      (node (ref "R40") (pin "2") (pinfunction "2_2") (pintype "passive"))
    )
    (net (code "11") (name "AC2-A") (class "Default")
      (node (ref "C5") (pin "1") (pinfunction "1_1") (pintype "passive"))
      (node (ref "OP2") (pin "10") (pinfunction "+IN_10") (pintype "input"))
      (node (ref "R43") (pin "2") (pinfunction "2_2") (pintype "passive"))
    )
    (net (code "12") (name "AC2-B") (class "Default")
      (node (ref "C4") (pin "1") (pinfunction "1_1") (pintype "passive"))
      (node (ref "OP2") (pin "12") (pinfunction "+IN_12") (pintype "input"))
      (node (ref "R42") (pin "2") (pinfunction "2_2") (pintype "passive"))
    )
    (net (code "13") (name "CI1") (class "Default")
      (node (ref "R3") (pin "2") (pinfunction "2_2") (pintype "passive"))
      (node (ref "SC1") (pin "O") (pinfunction "O_O") (pintype "passive"))
    )
    (net (code "14") (name "CI2") (class "Default")
      (node (ref "R6") (pin "2") (pinfunction "2_2") (pintype "passive"))
      (node (ref "SC2") (pin "O") (pinfunction "O_O") (pintype "passive"))
    )
    (net (code "15") (name "CI3") (class "Default")
      (node (ref "R9") (pin "2") (pinfunction "2_2") (pintype "passive"))
      (node (ref "SC3") (pin "O") (pinfunction "O_O") (pintype "passive"))
    )
    (net (code "16") (name "CI4") (class "Default")
      (node (ref "R12") (pin "2") (pinfunction "2_2") (pintype "passive"))
      (node (ref "SC4") (pin "O") (pinfunction "O_O") (pintype "passive"))
    )
    (net (code "17") (name "DAC1") (class "Default")
      (node (ref "OP2") (pin "1") (pinfunction "OUT_1") (pintype "output"))
      (node (ref "R15") (pin "2") (pinfunction "2_2") (pintype "passive"))
      (node (ref "RT1") (pin "1") (pinfunction "A_1") (pintype "passive"))
      (node (ref "SC1") (pin "S") (pinfunction "S_S") (pintype "passive"))
    )
    (net (code "18") (name "DAC2") (class "Default")
      (node (ref "OP2") (pin "7") (pinfunction "OUT_7") (pintype "output"))
      (node (ref "R16") (pin "2") (pinfunction "2_2") (pintype "passive"))
      (node (ref "RT2") (pin "1") (pinfunction "A_1") (pintype "passive"))
      (node (ref "SC2") (pin "S") (pinfunction "S_S") (pintype "passive"))
    )
    (net (code "19") (name "DAC3") (class "Default")
      (node (ref "OP2") (pin "14") (pinfunction "OUT_14") (pintype "output"))
      (node (ref "R17") (pin "2") (pinfunction "2_2") (pintype "passive"))
      (node (ref "RT3") (pin "1") (pinfunction "A_1") (pintype "passive"))
      (node (ref "SC3") (pin "S") (pinfunction "S_S") (pintype "passive"))
    )
    (net (code "20") (name "DAC4") (class "Default")
      (node (ref "OP2") (pin "8") (pinfunction "OUT_8") (pintype "output"))
      (node (ref "R18") (pin "2") (pinfunction "2_2") (pintype "passive"))
      (node (ref "RT4") (pin "1") (pinfunction "A_1") (pintype "passive"))
      (node (ref "SC4") (pin "S") (pinfunction "S_S") (pintype "passive"))
    )
    (net (code "21") (name "DC") (class "Default")
      (node (ref "OLED") (pin "DC") (pinfunction "DC_DC") (pintype "input"))
      (node (ref "SHIELD") (pin "D4") (pinfunction "D4_D4") (pintype "bidirectional"))
    )
    (net (code "22") (name "ENCA") (class "Default")
      (node (ref "EN1") (pin "A") (pinfunction "A_A") (pintype "passive"))
      (node (ref "SHIELD") (pin "D10") (pinfunction "*D10_D10") (pintype "bidirectional"))
    )
    (net (code "23") (name "ENCB") (class "Default")
      (node (ref "EN1") (pin "B") (pinfunction "B_B") (pintype "passive"))
      (node (ref "SHIELD") (pin "D9") (pinfunction "*D9_D9") (pintype "bidirectional"))
    )
    (net (code "24") (name "ENCS") (class "Default")
      (node (ref "EN1") (pin "D") (pinfunction "1_D") (pintype "passive"))
      (node (ref "R39") (pin "1") (pinfunction "1_1") (pintype "passive"))
      (node (ref "SHIELD") (pin "D12") (pinfunction "D12_D12") (pintype "bidirectional"))
    )
    (net (code "25") (name "GND") (class "Default")
      (node (ref "AC1") (pin "12") (pinfunction "AVSS_12") (pintype "power_in"))
      (node (ref "AC2") (pin "12") (pinfunction "AVSS_12") (pintype "power_in"))
      (node (ref "C1") (pin "2") (pinfunction "2_2") (pintype "passive"))
      (node (ref "C2") (pin "2") (pinfunction "2_2") (pintype "passive"))
      (node (ref "C3") (pin "2") (pinfunction "2_2") (pintype "passive"))
      (node (ref "C4") (pin "2") (pinfunction "2_2") (pintype "passive"))
      (node (ref "C5") (pin "2") (pinfunction "2_2") (pintype "passive"))
      (node (ref "CI1") (pin "P$3") (pinfunction "1_P$3") (pintype "passive"))
      (node (ref "CI2") (pin "P$3") (pinfunction "1_P$3") (pintype "passive"))
      (node (ref "CI3") (pin "P$3") (pinfunction "1_P$3") (pintype "passive"))
      (node (ref "CI4") (pin "P$3") (pinfunction "1_P$3") (pintype "passive"))
      (node (ref "CO1") (pin "P$2") (pinfunction "3_P$2") (pintype "passive"))
      (node (ref "CO1") (pin "P$3") (pinfunction "1_P$3") (pintype "passive"))
      (node (ref "CO2") (pin "P$2") (pinfunction "3_P$2") (pintype "passive"))
      (node (ref "CO2") (pin "P$3") (pinfunction "1_P$3") (pintype "passive"))
      (node (ref "CO3") (pin "P$2") (pinfunction "3_P$2") (pintype "passive"))
      (node (ref "CO3") (pin "P$3") (pinfunction "1_P$3") (pintype "passive"))
      (node (ref "CO4") (pin "P$2") (pinfunction "3_P$2") (pintype "passive"))
      (node (ref "CO4") (pin "P$3") (pinfunction "1_P$3") (pintype "passive"))
      (node (ref "D2") (pin "A") (pinfunction "A_A") (pintype "passive"))
      (node (ref "D4") (pin "A") (pinfunction "A_A") (pintype "passive"))
      (node (ref "D6") (pin "A") (pinfunction "A_A") (pintype "passive"))
      (node (ref "D8") (pin "A") (pinfunction "A_A") (pintype "passive"))
      (node (ref "DC1") (pin "2") (pinfunction "2_2") (pintype "passive"))
      (node (ref "DC2") (pin "2") (pinfunction "2_2") (pintype "passive"))
      (node (ref "DC3") (pin "2") (pinfunction "2_2") (pintype "passive"))
      (node (ref "DC4") (pin "2") (pinfunction "2_2") (pintype "passive"))
      (node (ref "EN1") (pin "C") (pinfunction "C_C") (pintype "passive"))
      (node (ref "EN1") (pin "E") (pinfunction "3_E") (pintype "passive"))
      (node (ref "FNC") (pin "P$2") (pinfunction "3_P$2") (pintype "passive"))
      (node (ref "FNC") (pin "P$3") (pinfunction "1_P$3") (pintype "passive"))
      (node (ref "GT1") (pin "P$2") (pinfunction "3_P$2") (pintype "passive"))
      (node (ref "GT1") (pin "P$3") (pinfunction "1_P$3") (pintype "passive"))
      (node (ref "GT2") (pin "P$2") (pinfunction "3_P$2") (pintype "passive"))
      (node (ref "GT2") (pin "P$3") (pinfunction "1_P$3") (pintype "passive"))
      (node (ref "GT3") (pin "P$3") (pinfunction "1_P$3") (pintype "passive"))
      (node (ref "GT4") (pin "P$3") (pinfunction "1_P$3") (pintype "passive"))
      (node (ref "I2C") (pin "1") (pinfunction "1_1") (pintype "passive"))
      (node (ref "I2C") (pin "2") (pinfunction "2_2") (pintype "passive"))
      (node (ref "OFT") (pin "P$3") (pinfunction "1_P$3") (pintype "passive"))
      (node (ref "OLED") (pin "GND") (pinfunction "GND_GND") (pintype "power_in"))
      (node (ref "PC1") (pin "-") (pinfunction "-_-") (pintype "passive"))
      (node (ref "PC2") (pin "+") (pinfunction "+_+") (pintype "passive"))
      (node (ref "PWR") (pin "3") (pinfunction "GND_3") (pintype "bidirectional"))
      (node (ref "PWR") (pin "4") (pinfunction "GND_4") (pintype "bidirectional"))
      (node (ref "PWR") (pin "5") (pinfunction "GND_5") (pintype "bidirectional"))
      (node (ref "PWR") (pin "6") (pinfunction "GND_6") (pintype "bidirectional"))
      (node (ref "PWR") (pin "7") (pinfunction "GND_7") (pintype "bidirectional"))
      (node (ref "PWR") (pin "8") (pinfunction "GND_8") (pintype "bidirectional"))
      (node (ref "Q1") (pin "E") (pinfunction "E_E") (pintype "passive"))
      (node (ref "Q2") (pin "E") (pinfunction "E_E") (pintype "passive"))
      (node (ref "Q3") (pin "E") (pinfunction "E_E") (pintype "passive"))
      (node (ref "Q4") (pin "E") (pinfunction "E_E") (pintype "passive"))
      (node (ref "R19") (pin "1") (pinfunction "1_1") (pintype "passive"))
      (node (ref "R22") (pin "1") (pinfunction "1_1") (pintype "passive"))
      (node (ref "R24") (pin "1") (pinfunction "1_1") (pintype "passive"))
      (node (ref "R27") (pin "1") (pinfunction "1_1") (pintype "passive"))
      (node (ref "R31") (pin "1") (pinfunction "1_1") (pintype "passive"))
      (node (ref "R35") (pin "1") (pinfunction "1_1") (pintype "passive"))
      (node (ref "R44") (pin "2") (pinfunction "2_2") (pintype "passive"))
      (node (ref "REF") (pin "2") (pinfunction "A_2") (pintype "passive"))
      (node (ref "SHIELD") (pin "GND@0") (pinfunction "GND_GND@0") (pintype "bidirectional"))
      (node (ref "SHIELD") (pin "GND@1") (pinfunction "GND_GND@1") (pintype "bidirectional"))
      (node (ref "SHIELD") (pin "GND@2") (pinfunction "GND_GND@2") (pintype "bidirectional"))
    )
    (net (code "26") (name "LDAC") (class "Default")
      (node (ref "AC1") (pin "8") (pinfunction "LDAC_8") (pintype "input"))
      (node (ref "AC2") (pin "8") (pinfunction "LDAC_8") (pintype "input"))
      (node (ref "SHIELD") (pin "D8") (pinfunction "D8_D8") (pintype "bidirectional"))
    )
    (net (code "27") (name "MOSI") (class "Default")
      (node (ref "AC1") (pin "5") (pinfunction "SDI_5") (pintype "input"))
      (node (ref "AC2") (pin "5") (pinfunction "SDI_5") (pintype "input"))
      (node (ref "OLED") (pin "SDA") (pinfunction "DATA_SDA") (pintype "output"))
      (node (ref "SHIELD") (pin "D11") (pinfunction "*D11_D11") (pintype "bidirectional"))
    )
    (net (code "28") (name "Net-(AC1-DACA)") (class "Default")
      (node (ref "AC1") (pin "14") (pinfunction "DACA_14") (pintype "output"))
      (node (ref "R41") (pin "1") (pinfunction "1_1") (pintype "passive"))
    )
    (net (code "29") (name "Net-(AC1-DACB)") (class "Default")
      (node (ref "AC1") (pin "10") (pinfunction "DACB_10") (pintype "output"))
      (node (ref "R40") (pin "1") (pinfunction "1_1") (pintype "passive"))
    )
    (net (code "30") (name "Net-(AC2-DACA)") (class "Default")
      (node (ref "AC2") (pin "14") (pinfunction "DACA_14") (pintype "output"))
      (node (ref "R43") (pin "1") (pinfunction "1_1") (pintype "passive"))
    )
    (net (code "31") (name "Net-(AC2-DACB)") (class "Default")
      (node (ref "AC2") (pin "10") (pinfunction "DACB_10") (pintype "output"))
      (node (ref "R42") (pin "1") (pinfunction "1_1") (pintype "passive"))
    )
    (net (code "32") (name "Net-(ADA-X1)") (class "Default")
      (node (ref "AD") (pin "7") (pinfunction "X1_7") (pintype "input"))
      (node (ref "SC1") (pin "P") (pinfunction "P_P") (pintype "passive"))
    )
    (net (code "33") (name "Net-(ADA-X2)") (class "Default")
      (node (ref "AD") (pin "8") (pinfunction "X2_8") (pintype "input"))
      (node (ref "SC2") (pin "P") (pinfunction "P_P") (pintype "passive"))
    )
    (net (code "34") (name "Net-(ADA-Y1)") (class "Default")
      (node (ref "AD") (pin "1") (pinfunction "Y1_1") (pintype "input"))
      (node (ref "SC3") (pin "P") (pinfunction "P_P") (pintype "passive"))
    )
    (net (code "35") (name "Net-(ADA-Y2)") (class "Default")
      (node (ref "AD") (pin "2") (pinfunction "Y2_2") (pintype "input"))
      (node (ref "SC4") (pin "P") (pinfunction "P_P") (pintype "passive"))
    )
    (net (code "36") (name "Net-(CI1-2)") (class "Default")
      (node (ref "CI1") (pin "P$1") (pinfunction "2_P$1") (pintype "passive"))
      (node (ref "R1") (pin "1") (pinfunction "1_1") (pintype "passive"))
      (node (ref "R3") (pin "1") (pinfunction "1_1") (pintype "passive"))
    )
    (net (code "37") (name "Net-(CI1-3)") (class "Default")
      (node (ref "CI1") (pin "P$2") (pinfunction "3_P$2") (pintype "passive"))
      (node (ref "PR1") (pin "2") (pinfunction "S_2") (pintype "passive"))
    )
    (net (code "38") (name "Net-(CI2-2)") (class "Default")
      (node (ref "CI2") (pin "P$1") (pinfunction "2_P$1") (pintype "passive"))
      (node (ref "R4") (pin "1") (pinfunction "1_1") (pintype "passive"))
      (node (ref "R6") (pin "1") (pinfunction "1_1") (pintype "passive"))
    )
    (net (code "39") (name "Net-(CI2-3)") (class "Default")
      (node (ref "CI2") (pin "P$2") (pinfunction "3_P$2") (pintype "passive"))
      (node (ref "PR2") (pin "2") (pinfunction "S_2") (pintype "passive"))
    )
    (net (code "40") (name "Net-(CI3-2)") (class "Default")
      (node (ref "CI3") (pin "P$1") (pinfunction "2_P$1") (pintype "passive"))
      (node (ref "R7") (pin "1") (pinfunction "1_1") (pintype "passive"))
      (node (ref "R9") (pin "1") (pinfunction "1_1") (pintype "passive"))
    )
    (net (code "41") (name "Net-(CI3-3)") (class "Default")
      (node (ref "CI3") (pin "P$2") (pinfunction "3_P$2") (pintype "passive"))
      (node (ref "PR3") (pin "2") (pinfunction "S_2") (pintype "passive"))
    )
    (net (code "42") (name "Net-(CI4-2)") (class "Default")
      (node (ref "CI4") (pin "P$1") (pinfunction "2_P$1") (pintype "passive"))
      (node (ref "R10") (pin "1") (pinfunction "1_1") (pintype "passive"))
      (node (ref "R12") (pin "1") (pinfunction "1_1") (pintype "passive"))
    )
    (net (code "43") (name "Net-(CI4-3)") (class "Default")
      (node (ref "CI4") (pin "P$2") (pinfunction "3_P$2") (pintype "passive"))
      (node (ref "PR4") (pin "2") (pinfunction "S_2") (pintype "passive"))
    )
    (net (code "44") (name "Net-(CO1-2)") (class "Default")
      (node (ref "CO1") (pin "P$1") (pinfunction "2_P$1") (pintype "passive"))
      (node (ref "R15") (pin "1") (pinfunction "1_1") (pintype "passive"))
    )
    (net (code "45") (name "Net-(CO2-2)") (class "Default")
      (node (ref "CO2") (pin "P$1") (pinfunction "2_P$1") (pintype "passive"))
      (node (ref "R16") (pin "1") (pinfunction "1_1") (pintype "passive"))
    )
    (net (code "46") (name "Net-(CO3-2)") (class "Default")
      (node (ref "CO3") (pin "P$1") (pinfunction "2_P$1") (pintype "passive"))
      (node (ref "R17") (pin "1") (pinfunction "1_1") (pintype "passive"))
    )
    (net (code "47") (name "Net-(CO4-2)") (class "Default")
      (node (ref "CO4") (pin "P$1") (pinfunction "2_P$1") (pintype "passive"))
      (node (ref "R18") (pin "1") (pinfunction "1_1") (pintype "passive"))
    )
    (net (code "48") (name "Net-(FB1-Pad1)") (class "Default")
      (node (ref "FB1") (pin "1") (pinfunction "1_1") (pintype "passive"))
      (node (ref "SD1") (pin "C") (pinfunction "C_C") (pintype "passive"))
    )
    (net (code "49") (name "Net-(FB2-Pad1)") (class "Default")
      (node (ref "FB2") (pin "1") (pinfunction "1_1") (pintype "passive"))
      (node (ref "SD2") (pin "A") (pinfunction "A_A") (pintype "passive"))
    )
    (net (code "50") (name "Net-(FNC-2)") (class "Default")
      (node (ref "FNC") (pin "P$1") (pinfunction "2_P$1") (pintype "passive"))
      (node (ref "R14") (pin "1") (pinfunction "1_1") (pintype "passive"))
    )
    (net (code "51") (name "Net-(GT1-2)") (class "Default")
      (node (ref "GT1") (pin "P$1") (pinfunction "2_P$1") (pintype "passive"))
      (node (ref "R33") (pin "1") (pinfunction "1_1") (pintype "passive"))
      (node (ref "R34") (pin "1") (pinfunction "1_1") (pintype "passive"))
    )
    (net (code "52") (name "Net-(GT2-2)") (class "Default")
      (node (ref "GT2") (pin "P$1") (pinfunction "2_P$1") (pintype "passive"))
      (node (ref "R29") (pin "1") (pinfunction "1_1") (pintype "passive"))
      (node (ref "R30") (pin "1") (pinfunction "1_1") (pintype "passive"))
    )
    (net (code "53") (name "Net-(GT3-2)") (class "Default")
      (node (ref "GT3") (pin "P$1") (pinfunction "2_P$1") (pintype "passive"))
      (node (ref "R25") (pin "1") (pinfunction "1_1") (pintype "passive"))
      (node (ref "R26") (pin "1") (pinfunction "1_1") (pintype "passive"))
    )
    (net (code "54") (name "Net-(GT3-3)") (class "Default")
      (node (ref "D9") (pin "C") (pinfunction "C_C") (pintype "passive"))
      (node (ref "GT3") (pin "P$2") (pinfunction "3_P$2") (pintype "passive"))
      (node (ref "R24") (pin "2") (pinfunction "2_2") (pintype "passive"))
    )
    (net (code "55") (name "Net-(GT4-2)") (class "Default")
      (node (ref "GT4") (pin "P$1") (pinfunction "2_P$1") (pintype "passive"))
      (node (ref "R20") (pin "1") (pinfunction "1_1") (pintype "passive"))
      (node (ref "R21") (pin "1") (pinfunction "1_1") (pintype "passive"))
    )
    (net (code "56") (name "Net-(GT4-3)") (class "Default")
      (node (ref "D10") (pin "C") (pinfunction "C_C") (pintype "passive"))
      (node (ref "GT4") (pin "P$2") (pinfunction "3_P$2") (pintype "passive"))
      (node (ref "R19") (pin "2") (pinfunction "2_2") (pintype "passive"))
    )
    (net (code "57") (name "Net-(I2C-Pad3)") (class "Default")
      (node (ref "I2C") (pin "3") (pinfunction "3_3") (pintype "passive"))
      (node (ref "I2C") (pin "4") (pinfunction "4_4") (pintype "passive"))
      (node (ref "R50") (pin "1") (pinfunction "1_1") (pintype "passive"))
      (node (ref "SHIELD") (pin "SDA") (pinfunction "SDA_SDA") (pintype "bidirectional"))
    )
    (net (code "58") (name "Net-(I2C-Pad5)") (class "Default")
      (node (ref "I2C") (pin "5") (pinfunction "5_5") (pintype "passive"))
      (node (ref "I2C") (pin "6") (pinfunction "6_6") (pintype "passive"))
      (node (ref "R49") (pin "1") (pinfunction "1_1") (pintype "passive"))
      (node (ref "SHIELD") (pin "SCL") (pinfunction "SCL_SCL") (pintype "bidirectional"))
    )
    (net (code "59") (name "Net-(OFT-2)") (class "Default")
      (node (ref "OFT") (pin "P$1") (pinfunction "2_P$1") (pintype "passive"))
      (node (ref "R13") (pin "1") (pinfunction "1_1") (pintype "passive"))
    )
    (net (code "60") (name "Net-(OFT-3)") (class "Default")
      (node (ref "OFT") (pin "P$2") (pinfunction "3_P$2") (pintype "passive"))
      (node (ref "PR5") (pin "2") (pinfunction "S_2") (pintype "passive"))
    )
    (net (code "61") (name "Net-(OLED-RST)") (class "Default")
      (node (ref "C1") (pin "1") (pinfunction "1_1") (pintype "passive"))
      (node (ref "D11") (pin "A") (pinfunction "A_A") (pintype "passive"))
      (node (ref "OLED") (pin "RES") (pinfunction "RST_RES") (pintype "input"))
      (node (ref "R37") (pin "2") (pinfunction "2_2") (pintype "passive"))
    )
    (net (code "62") (name "Net-(OP1A-+IN)") (class "Default")
      (node (ref "OP1") (pin "3") (pinfunction "+IN_3") (pintype "input"))
      (node (ref "R38") (pin "1") (pinfunction "1_1") (pintype "passive"))
      (node (ref "REF") (pin "1") (pinfunction "C_1") (pintype "passive"))
    )
    (net (code "63") (name "Net-(OP1B-+IN)") (class "Default")
      (node (ref "OP1") (pin "5") (pinfunction "+IN_5") (pintype "input"))
      (node (ref "R44") (pin "1") (pinfunction "1_1") (pintype "passive"))
      (node (ref "RT5") (pin "2") (pinfunction "S_2") (pintype "passive"))
    )
    (net (code "64") (name "Net-(OP1B--IN)") (class "Default")
      (node (ref "OP1") (pin "6") (pinfunction "-IN_6") (pintype "input"))
      (node (ref "OP1") (pin "7") (pinfunction "OUT_7") (pintype "output"))
      (node (ref "R45") (pin "1") (pinfunction "1_1") (pintype "passive"))
      (node (ref "R46") (pin "1") (pinfunction "1_1") (pintype "passive"))
      (node (ref "R47") (pin "1") (pinfunction "1_1") (pintype "passive"))
      (node (ref "R48") (pin "1") (pinfunction "1_1") (pintype "passive"))
    )
    (net (code "65") (name "Net-(OP2A--IN)") (class "Default")
      (node (ref "OP2") (pin "2") (pinfunction "-IN_2") (pintype "input"))
      (node (ref "R45") (pin "2") (pinfunction "2_2") (pintype "passive"))
      (node (ref "RT1") (pin "2") (pinfunction "S_2") (pintype "passive"))
    )
    (net (code "66") (name "Net-(OP2B--IN)") (class "Default")
      (node (ref "OP2") (pin "6") (pinfunction "-IN_6") (pintype "input"))
      (node (ref "R46") (pin "2") (pinfunction "2_2") (pintype "passive"))
      (node (ref "RT2") (pin "2") (pinfunction "S_2") (pintype "passive"))
    )
    (net (code "67") (name "Net-(OP2C--IN)") (class "Default")
      (node (ref "OP2") (pin "9") (pinfunction "-IN_9") (pintype "input"))
      (node (ref "R47") (pin "2") (pinfunction "2_2") (pintype "passive"))
      (node (ref "RT4") (pin "2") (pinfunction "S_2") (pintype "passive"))
    )
    (net (code "68") (name "Net-(OP2D--IN)") (class "Default")
      (node (ref "OP2") (pin "13") (pinfunction "-IN_13") (pintype "input"))
      (node (ref "R48") (pin "2") (pinfunction "2_2") (pintype "passive"))
      (node (ref "RT3") (pin "2") (pinfunction "S_2") (pintype "passive"))
    )
    (net (code "69") (name "Net-(PB1-P)") (class "Default")
      (node (ref "D9") (pin "A") (pinfunction "A_A") (pintype "passive"))
      (node (ref "PB1") (pin "3") (pinfunction "P_3") (pintype "passive"))
    )
    (net (code "70") (name "Net-(PB2-P)") (class "Default")
      (node (ref "D10") (pin "A") (pinfunction "A_A") (pintype "passive"))
      (node (ref "PB2") (pin "3") (pinfunction "P_3") (pintype "passive"))
    )
    (net (code "71") (name "Net-(PSW-O)") (class "Default")
      (node (ref "PSW") (pin "1") (pinfunction "O_1") (pintype "passive"))
      (node (ref "SHIELD") (pin "TX") (pinfunction "TX_TX") (pintype "bidirectional"))
    )
    (net (code "72") (name "Net-(PSW-O1)") (class "Default")
      (node (ref "PSW") (pin "4") (pinfunction "O1_4") (pintype "passive"))
      (node (ref "SHIELD") (pin "RX") (pinfunction "RX_RX") (pintype "bidirectional"))
    )
    (net (code "73") (name "Net-(PWR-+12V-Pad10)") (class "Default")
      (node (ref "PWR") (pin "10") (pinfunction "+12V_10") (pintype "bidirectional"))
      (node (ref "PWR") (pin "9") (pinfunction "+12V_9") (pintype "bidirectional"))
      (node (ref "SD1") (pin "A") (pinfunction "A_A") (pintype "passive"))
    )
    (net (code "74") (name "Net-(PWR--12V-Pad1)") (class "Default")
      (node (ref "PWR") (pin "1") (pinfunction "-12V_1") (pintype "bidirectional"))
      (node (ref "PWR") (pin "2") (pinfunction "-12V_2") (pintype "bidirectional"))
      (node (ref "SD2") (pin "C") (pinfunction "C_C") (pintype "passive"))
    )
    (net (code "75") (name "Net-(Q1-PadB)") (class "Default")
      (node (ref "Q1") (pin "B") (pinfunction "B_B") (pintype "passive"))
      (node (ref "R21") (pin "2") (pinfunction "2_2") (pintype "passive"))
      (node (ref "R22") (pin "2") (pinfunction "2_2") (pintype "passive"))
    )
    (net (code "76") (name "Net-(Q1-PadC)") (class "Default")
      (node (ref "Q1") (pin "C") (pinfunction "C_C") (pintype "passive"))
      (node (ref "R23") (pin "1") (pinfunction "1_1") (pintype "passive"))
      (node (ref "SG4") (pin "S") (pinfunction "S_S") (pintype "passive"))
    )
    (net (code "77") (name "Net-(Q2-PadB)") (class "Default")
      (node (ref "Q2") (pin "B") (pinfunction "B_B") (pintype "passive"))
      (node (ref "R26") (pin "2") (pinfunction "2_2") (pintype "passive"))
      (node (ref "R27") (pin "2") (pinfunction "2_2") (pintype "passive"))
    )
    (net (code "78") (name "Net-(Q2-PadC)") (class "Default")
      (node (ref "Q2") (pin "C") (pinfunction "C_C") (pintype "passive"))
      (node (ref "R28") (pin "1") (pinfunction "1_1") (pintype "passive"))
      (node (ref "SG3") (pin "S") (pinfunction "S_S") (pintype "passive"))
    )
    (net (code "79") (name "Net-(Q3-PadB)") (class "Default")
      (node (ref "Q3") (pin "B") (pinfunction "B_B") (pintype "passive"))
      (node (ref "R30") (pin "2") (pinfunction "2_2") (pintype "passive"))
      (node (ref "R31") (pin "2") (pinfunction "2_2") (pintype "passive"))
    )
    (net (code "80") (name "Net-(Q3-PadC)") (class "Default")
      (node (ref "Q3") (pin "C") (pinfunction "C_C") (pintype "passive"))
      (node (ref "R32") (pin "1") (pinfunction "1_1") (pintype "passive"))
      (node (ref "SG2") (pin "S") (pinfunction "S_S") (pintype "passive"))
    )
    (net (code "81") (name "Net-(Q4-PadB)") (class "Default")
      (node (ref "Q4") (pin "B") (pinfunction "B_B") (pintype "passive"))
      (node (ref "R34") (pin "2") (pinfunction "2_2") (pintype "passive"))
      (node (ref "R35") (pin "2") (pinfunction "2_2") (pintype "passive"))
    )
    (net (code "82") (name "Net-(Q4-PadC)") (class "Default")
      (node (ref "Q4") (pin "C") (pinfunction "C_C") (pintype "passive"))
      (node (ref "R36") (pin "1") (pinfunction "1_1") (pintype "passive"))
      (node (ref "SG1") (pin "S") (pinfunction "S_S") (pintype "passive"))
    )
    (net (code "83") (name "Net-(R20-Pad2)") (class "Default")
      (node (ref "R20") (pin "2") (pinfunction "2_2") (pintype "passive"))
      (node (ref "SG4") (pin "O") (pinfunction "O_O") (pintype "passive"))
    )
    (net (code "84") (name "Net-(R25-Pad2)") (class "Default")
      (node (ref "R25") (pin "2") (pinfunction "2_2") (pintype "passive"))
      (node (ref "SG3") (pin "O") (pinfunction "O_O") (pintype "passive"))
    )
    (net (code "85") (name "Net-(R29-Pad2)") (class "Default")
      (node (ref "R29") (pin "2") (pinfunction "2_2") (pintype "passive"))
      (node (ref "SG2") (pin "O") (pinfunction "O_O") (pintype "passive"))
    )
    (net (code "86") (name "Net-(R33-Pad2)") (class "Default")
      (node (ref "R33") (pin "2") (pinfunction "2_2") (pintype "passive"))
      (node (ref "SG1") (pin "O") (pinfunction "O_O") (pintype "passive"))
    )
    (net (code "87") (name "PD0") (class "Default")
      (node (ref "PSW") (pin "5") (pinfunction "P1_5") (pintype "passive"))
      (node (ref "SG1") (pin "P") (pinfunction "P_P") (pintype "passive"))
    )
    (net (code "88") (name "PD1") (class "Default")
      (node (ref "PSW") (pin "2") (pinfunction "P_2") (pintype "passive"))
      (node (ref "SG2") (pin "P") (pinfunction "P_P") (pintype "passive"))
    )
    (net (code "89") (name "PD2") (class "Default")
      (node (ref "SG3") (pin "P") (pinfunction "P_P") (pintype "passive"))
      (node (ref "SHIELD") (pin "D2") (pinfunction "D2_D2") (pintype "bidirectional"))
    )
    (net (code "90") (name "PD3") (class "Default")
      (node (ref "SG4") (pin "P") (pinfunction "P_P") (pintype "passive"))
      (node (ref "SHIELD") (pin "D3") (pinfunction "*D3_D3") (pintype "bidirectional"))
    )
    (net (code "91") (name "SCK") (class "Default")
      (node (ref "AC1") (pin "4") (pinfunction "SCK_4") (pintype "input"))
      (node (ref "AC2") (pin "4") (pinfunction "SCK_4") (pintype "input"))
      (node (ref "OLED") (pin "SCK") (pinfunction "CLK_SCK") (pintype "input"))
      (node (ref "SHIELD") (pin "D13") (pinfunction "D13_D13") (pintype "bidirectional"))
    )
    (net (code "92") (name "SS0") (class "Default")
      (node (ref "AC1") (pin "3") (pinfunction "#CS_3") (pintype "input"))
      (node (ref "SHIELD") (pin "D7") (pinfunction "D7_D7") (pintype "bidirectional"))
    )
    (net (code "93") (name "SS1") (class "Default")
      (node (ref "AC2") (pin "3") (pinfunction "#CS_3") (pintype "input"))
      (node (ref "SHIELD") (pin "D6") (pinfunction "*D6_D6") (pintype "bidirectional"))
    )
    (net (code "94") (name "SS2") (class "Default")
      (node (ref "OLED") (pin "CS") (pinfunction "CS_CS") (pintype "output"))
      (node (ref "SHIELD") (pin "D5") (pinfunction "*D5_D5") (pintype "bidirectional"))
    )
    (net (code "95") (name "VREF") (class "Default")
      (node (ref "AC1") (pin "11") (pinfunction "REFB_11") (pintype "input"))
      (node (ref "AC1") (pin "13") (pinfunction "REFA_13") (pintype "input"))
      (node (ref "AC2") (pin "11") (pinfunction "REFB_11") (pintype "input"))
      (node (ref "AC2") (pin "13") (pinfunction "REFA_13") (pintype "input"))
      (node (ref "OP1") (pin "1") (pinfunction "OUT_1") (pintype "output"))
      (node (ref "OP1") (pin "2") (pinfunction "-IN_2") (pintype "input"))
      (node (ref "RT5") (pin "1") (pinfunction "A_1") (pintype "passive"))
      (node (ref "SHIELD") (pin "AREF") (pinfunction "AREF_AREF") (pintype "bidirectional"))
    )
    (net (code "96") (name "W") (class "Default")
      (node (ref "AD") (pin "5") (pinfunction "W_5") (pintype "output"))
      (node (ref "R14") (pin "2") (pinfunction "2_2") (pintype "passive"))
    )
    (net (code "97") (name "Z") (class "Default")
      (node (ref "AD") (pin "4") (pinfunction "Z_4") (pintype "input"))
      (node (ref "R13") (pin "2") (pinfunction "2_2") (pintype "passive"))
    )
    (net (code "98") (name "unconnected-(PB1-P1-Pad4)") (class "Default")
      (node (ref "PB1") (pin "4") (pinfunction "P1_4") (pintype "passive"))
    )
    (net (code "99") (name "unconnected-(PB1-S1-Pad2)") (class "Default")
      (node (ref "PB1") (pin "2") (pinfunction "S1_2") (pintype "passive"))
    )
    (net (code "100") (name "unconnected-(PB2-P1-Pad4)") (class "Default")
      (node (ref "PB2") (pin "4") (pinfunction "P1_4") (pintype "passive"))
    )
    (net (code "101") (name "unconnected-(PB2-S1-Pad2)") (class "Default")
      (node (ref "PB2") (pin "2") (pinfunction "S1_2") (pintype "passive"))
    )
    (net (code "102") (name "unconnected-(PSW-S-Pad3)") (class "Default")
      (node (ref "PSW") (pin "3") (pinfunction "S_3") (pintype "passive"))
    )
    (net (code "103") (name "unconnected-(PSW-S1-Pad6)") (class "Default")
      (node (ref "PSW") (pin "6") (pinfunction "S1_6") (pintype "passive"))
    )
    (net (code "104") (name "unconnected-(RT1-E-Pad3)") (class "Default")
      (node (ref "RT1") (pin "3") (pinfunction "E_3") (pintype "passive"))
    )
    (net (code "105") (name "unconnected-(RT2-E-Pad3)") (class "Default")
      (node (ref "RT2") (pin "3") (pinfunction "E_3") (pintype "passive"))
    )
    (net (code "106") (name "unconnected-(RT3-E-Pad3)") (class "Default")
      (node (ref "RT3") (pin "3") (pinfunction "E_3") (pintype "passive"))
    )
    (net (code "107") (name "unconnected-(RT4-E-Pad3)") (class "Default")
      (node (ref "RT4") (pin "3") (pinfunction "E_3") (pintype "passive"))
    )
    (net (code "108") (name "unconnected-(RT5-E-Pad3)") (class "Default")
      (node (ref "RT5") (pin "3") (pinfunction "E_3") (pintype "passive"))
    )
    (net (code "109") (name "unconnected-(SHIELD-PadA4)") (class "Default")
      (node (ref "SHIELD") (pin "A4") (pinfunction "A4_A4") (pintype "bidirectional"))
    )
    (net (code "110") (name "unconnected-(SHIELD-PadA5)") (class "Default")
      (node (ref "SHIELD") (pin "A5") (pinfunction "A5_A5") (pintype "bidirectional"))
    )
    (net (code "111") (name "unconnected-(SHIELD-PadIOREF)") (class "Default")
      (node (ref "SHIELD") (pin "IOREF") (pinfunction "IOREF_IOREF") (pintype "bidirectional"))
    )
    (net (code "112") (name "unconnected-(SHIELD-PadRES)") (class "Default")
      (node (ref "SHIELD") (pin "RES") (pinfunction "RES_RES") (pintype "bidirectional"))
    )
  )
)
